# 02-POWER_DC-DC.net
KiCad netlist of a schematic drawn in Altium Designer
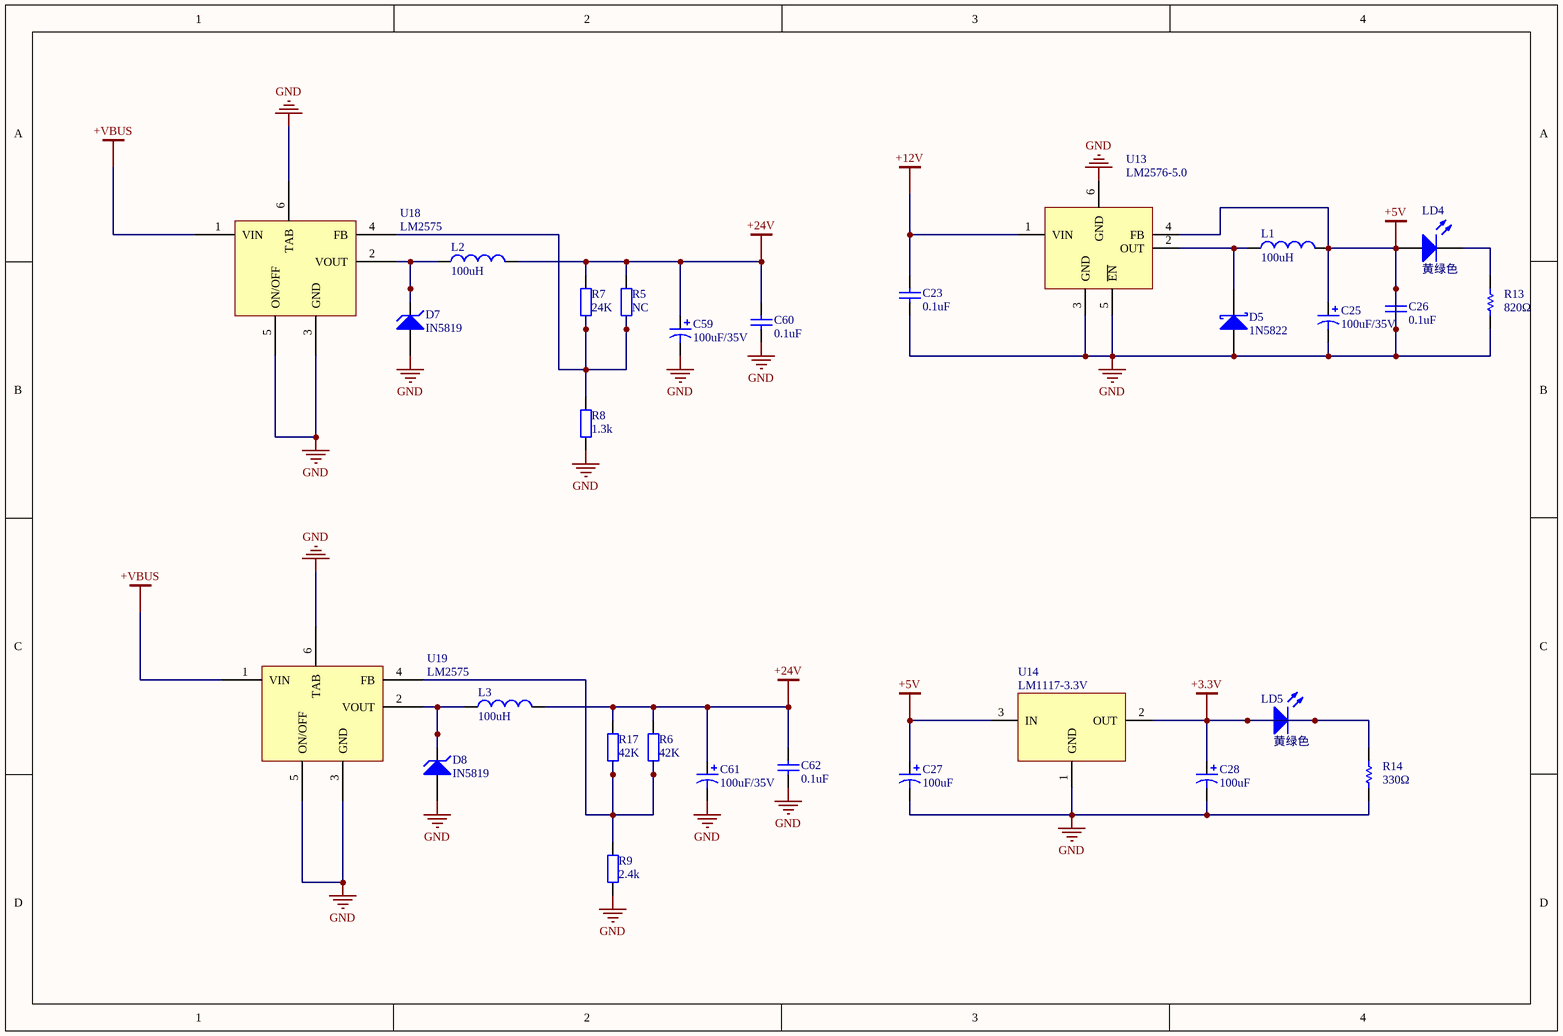
[diagram p0: 02-POWER DC-DC.SchDoc]

(export (version "E")
  (design (tool "Eeschema 10.0.6"))
  (components
    (comp (ref "C23")
      (value "0.1uF")
      (footprint "C0805")
      (description "Capacitor")
      (fields (field (name "Comment") "Cap") (field (name "PUBLISHER") "Altium Limited"))
      (libsource (lib "Lib") (part "Cap"))
    )
    (comp (ref "C25")
      (value "100uF/35V")
      (footprint "SMD-6.3-7.7")
      (description "Polarized Capacitor (Axial)")
      (fields (field (name "Comment") "Cap Pol2") (field (name "PUBLISHER") "Altium Limited"))
      (libsource (lib "Lib") (part "Cap Pol2"))
    )
    (comp (ref "C26")
      (value "0.1uF")
      (footprint "C0805")
      (description "Capacitor")
      (fields (field (name "Comment") "Cap") (field (name "PUBLISHER") "Altium Limited"))
      (libsource (lib "Lib") (part "Cap"))
    )
    (comp (ref "C27")
      (value "100uF")
      (footprint "SMD-6.3-7.7")
      (description "Polarized Capacitor (Axial)")
      (fields (field (name "Comment") "Cap Pol2") (field (name "PUBLISHER") "Altium Limited"))
      (libsource (lib "Lib") (part "Cap Pol2"))
    )
    (comp (ref "C28")
      (value "100uF")
      (footprint "SMD-6.3-7.7")
      (description "Polarized Capacitor (Axial)")
      (fields (field (name "Comment") "Cap Pol2") (field (name "PUBLISHER") "Altium Limited"))
      (libsource (lib "Lib") (part "Cap Pol2"))
    )
    (comp (ref "C59")
      (value "100uF/35V")
      (footprint "SMD-6.3-7.7")
      (description "Polarized Capacitor (Axial)")
      (fields (field (name "Comment") "Cap Pol2") (field (name "PUBLISHER") "Altium Limited"))
      (libsource (lib "Lib") (part "Cap Pol2"))
    )
    (comp (ref "C60")
      (value "0.1uF")
      (footprint "C0805")
      (description "Capacitor")
      (fields (field (name "Comment") "Cap") (field (name "PUBLISHER") "Altium Limited"))
      (libsource (lib "Lib") (part "Cap"))
    )
    (comp (ref "C61")
      (value "100uF/35V")
      (footprint "SMD-6.3-7.7")
      (description "Polarized Capacitor (Axial)")
      (fields (field (name "Comment") "Cap Pol2") (field (name "PUBLISHER") "Altium Limited"))
      (libsource (lib "Lib") (part "Cap Pol2"))
    )
    (comp (ref "C62")
      (value "0.1uF")
      (footprint "C0805")
      (description "Capacitor")
      (fields (field (name "Comment") "Cap") (field (name "PUBLISHER") "Altium Limited"))
      (libsource (lib "Lib") (part "Cap"))
    )
    (comp (ref "D5")
      (value "1N5822")
      (footprint "SMA-L4")
      (description "Schottky Rectifier")
      (fields (field (name "PUBLISHER") "Altium Limited"))
      (libsource (lib "Lib") (part "Diode 10TQ035"))
    )
    (comp (ref "D7")
      (value "IN5819")
      (footprint "SMA-L4")
      (description "Zener Diode")
      (fields (field (name "PUBLISHER") "Altium Limited"))
      (libsource (lib "Lib") (part "D Zener"))
    )
    (comp (ref "D8")
      (value "IN5819")
      (footprint "SMA-L4")
      (description "Zener Diode")
      (fields (field (name "PUBLISHER") "Altium Limited"))
      (libsource (lib "Lib") (part "D Zener"))
    )
    (comp (ref "L1")
      (value "100uH")
      (footprint "L100uH")
      (description "Inductor")
      (fields (field (name "PUBLISHER") "Altium Limited"))
      (libsource (lib "Lib") (part "Inductor"))
    )
    (comp (ref "L2")
      (value "100uH")
      (footprint "L100uH")
      (description "Inductor")
      (fields (field (name "PUBLISHER") "Altium Limited"))
      (libsource (lib "Lib") (part "Inductor"))
    )
    (comp (ref "L3")
      (value "100uH")
      (footprint "L100uH")
      (description "Inductor")
      (fields (field (name "PUBLISHER") "Altium Limited"))
      (libsource (lib "Lib") (part "Inductor"))
    )
    (comp (ref "LD4")
      (value "黄绿色")
      (footprint "LED0805")
      (description "Typical INFRARED GaAs LED")
      (fields (field (name "PUBLISHER") "Altium Limited"))
      (libsource (lib "Lib") (part "LED0"))
    )
    (comp (ref "LD5")
      (value "黄绿色")
      (footprint "LED0805")
      (description "Typical INFRARED GaAs LED")
      (fields (field (name "PUBLISHER") "Altium Limited"))
      (libsource (lib "Lib") (part "LED0"))
    )
    (comp (ref "R5")
      (value "NC")
      (footprint "R0805")
      (description "Resistor")
      (fields (field (name "Comment") "Res2") (field (name "PUBLISHER") "Altium Limited"))
      (libsource (lib "") (part "Res2_1"))
    )
    (comp (ref "R6")
      (value "42K")
      (footprint "R0805")
      (description "Resistor")
      (fields (field (name "Comment") "Res2") (field (name "PUBLISHER") "Altium Limited"))
      (libsource (lib "") (part "Res2_1"))
    )
    (comp (ref "R7")
      (value "24K")
      (footprint "R0805")
      (description "Resistor")
      (fields (field (name "Comment") "Res2") (field (name "PUBLISHER") "Altium Limited"))
      (libsource (lib "Lib") (part "Res2"))
    )
    (comp (ref "R8")
      (value "1.3k")
      (footprint "R0805")
      (description "Resistor")
      (fields (field (name "Comment") "Res2") (field (name "PUBLISHER") "Altium Limited"))
      (libsource (lib "") (part "Res2_1"))
    )
    (comp (ref "R9")
      (value "2.4k")
      (footprint "R0805")
      (description "Resistor")
      (fields (field (name "Comment") "Res2") (field (name "PUBLISHER") "Altium Limited"))
      (libsource (lib "") (part "Res2_1"))
    )
    (comp (ref "R13")
      (value "820Ω")
      (footprint "NTC-10D9")
      (description "Resistor")
      (fields (field (name "PUBLISHER") "Altium Limited"))
      (libsource (lib "Lib") (part "Res1"))
    )
    (comp (ref "R14")
      (value "330Ω")
      (footprint "NTC-10D9")
      (description "Resistor")
      (fields (field (name "PUBLISHER") "Altium Limited"))
      (libsource (lib "Lib") (part "Res1"))
    )
    (comp (ref "R17")
      (value "42K")
      (footprint "R0805")
      (description "Resistor")
      (fields (field (name "Comment") "Res2") (field (name "PUBLISHER") "Altium Limited"))
      (libsource (lib "Lib") (part "Res2"))
    )
    (comp (ref "U13") (value "LM2576-5.0") (footprint "TO-263-5") (libsource (lib "Lib") (part "LM2576-5.0")))
    (comp (ref "U14") (value "LM1117-3.3V") (footprint "SOT-223") (libsource (lib "Lib") (part "LM1117")))
    (comp (ref "U18") (value "LM2575") (footprint "TO-263-5") (libsource (lib "Schlib1") (part "LM2575")))
    (comp (ref "U19") (value "LM2575") (footprint "TO-263-5") (libsource (lib "Schlib1") (part "LM2575")))
  )
  (nets
    (net (code "1") (name "+3.3V") (class "Default")
      (node (ref "C28") (pin "1") (pinfunction "1_1") (pintype "passive"))
      (node (ref "LD5") (pin "1") (pinfunction "A_1") (pintype "passive"))
      (node (ref "LD5") (pin "2") (pinfunction "K_2") (pintype "passive"))
      (node (ref "R14") (pin "2") (pinfunction "2_2") (pintype "passive"))
      (node (ref "U14") (pin "2") (pinfunction "OUT_2") (pintype "passive"))
    )
    (net (code "2") (name "+5V") (class "Default")
      (node (ref "C23") (pin "1") (pinfunction "1_1") (pintype "passive"))
      (node (ref "C25") (pin "1") (pinfunction "1_1") (pintype "passive"))
      (node (ref "C25") (pin "2") (pinfunction "2_2") (pintype "passive"))
      (node (ref "C26") (pin "1") (pinfunction "1_1") (pintype "passive"))
      (node (ref "C26") (pin "2") (pinfunction "2_2") (pintype "passive"))
      (node (ref "C27") (pin "1") (pinfunction "1_1") (pintype "passive"))
      (node (ref "C27") (pin "2") (pinfunction "2_2") (pintype "passive"))
      (node (ref "C28") (pin "2") (pinfunction "2_2") (pintype "passive"))
      (node (ref "C59") (pin "2") (pinfunction "2_2") (pintype "passive"))
      (node (ref "C60") (pin "1") (pinfunction "1_1") (pintype "passive"))
      (node (ref "C61") (pin "2") (pinfunction "2_2") (pintype "passive"))
      (node (ref "C62") (pin "1") (pinfunction "1_1") (pintype "passive"))
      (node (ref "D5") (pin "2") (pinfunction "A_2") (pintype "passive"))
      (node (ref "D7") (pin "1") (pinfunction "A_1") (pintype "passive"))
      (node (ref "D8") (pin "1") (pinfunction "A_1") (pintype "passive"))
      (node (ref "L1") (pin "2") (pinfunction "2_2") (pintype "passive"))
      (node (ref "LD4") (pin "1") (pinfunction "A_1") (pintype "passive"))
      (node (ref "R13") (pin "1") (pinfunction "1_1") (pintype "passive"))
      (node (ref "R14") (pin "1") (pinfunction "1_1") (pintype "passive"))
      (node (ref "R8") (pin "2") (pinfunction "2_2") (pintype "passive"))
      (node (ref "R9") (pin "2") (pinfunction "2_2") (pintype "passive"))
      (node (ref "U13") (pin "3") (pinfunction "GND_3") (pintype "passive"))
      (node (ref "U13") (pin "4") (pinfunction "FB_4") (pintype "passive"))
      (node (ref "U13") (pin "5") (pinfunction "~{EN}_5") (pintype "passive"))
      (node (ref "U13") (pin "6") (pinfunction "GND_6") (pintype "passive"))
      (node (ref "U14") (pin "1") (pinfunction "GND_1") (pintype "passive"))
      (node (ref "U14") (pin "3") (pinfunction "IN_3") (pintype "passive"))
      (node (ref "U18") (pin "3") (pinfunction "GND_3") (pintype "passive"))
      (node (ref "U18") (pin "5") (pinfunction "ON/OFF_5") (pintype "passive"))
      (node (ref "U18") (pin "6") (pinfunction "TAB_6") (pintype "passive"))
      (node (ref "U19") (pin "3") (pinfunction "GND_3") (pintype "passive"))
      (node (ref "U19") (pin "5") (pinfunction "ON/OFF_5") (pintype "passive"))
      (node (ref "U19") (pin "6") (pinfunction "TAB_6") (pintype "passive"))
    )
    (net (code "3") (name "+12V") (class "Default")
      (node (ref "C23") (pin "2") (pinfunction "2_2") (pintype "passive"))
      (node (ref "U13") (pin "1") (pinfunction "VIN_1") (pintype "passive"))
    )
    (net (code "4") (name "+24V") (class "Default")
      (node (ref "C59") (pin "1") (pinfunction "1_1") (pintype "passive"))
      (node (ref "C60") (pin "2") (pinfunction "2_2") (pintype "passive"))
      (node (ref "C61") (pin "1") (pinfunction "1_1") (pintype "passive"))
      (node (ref "C62") (pin "2") (pinfunction "2_2") (pintype "passive"))
      (node (ref "L2") (pin "2") (pinfunction "2_2") (pintype "passive"))
      (node (ref "L3") (pin "2") (pinfunction "2_2") (pintype "passive"))
      (node (ref "R17") (pin "2") (pinfunction "2_2") (pintype "passive"))
      (node (ref "R5") (pin "1") (pinfunction "1_1") (pintype "passive"))
      (node (ref "R6") (pin "1") (pinfunction "1_1") (pintype "passive"))
      (node (ref "R7") (pin "2") (pinfunction "2_2") (pintype "passive"))
    )
    (net (code "5") (name "+VBUS") (class "Default")
      (node (ref "U18") (pin "1") (pinfunction "VIN_1") (pintype "passive"))
      (node (ref "U19") (pin "1") (pinfunction "VIN_1") (pintype "passive"))
    )
    (net (code "6") (name "Net-(D5-K)") (class "Default")
      (node (ref "D5") (pin "1") (pinfunction "K_1") (pintype "passive"))
      (node (ref "L1") (pin "1") (pinfunction "1_1") (pintype "passive"))
      (node (ref "U13") (pin "2") (pinfunction "OUT_2") (pintype "passive"))
    )
    (net (code "7") (name "Net-(D7-K)") (class "Default")
      (node (ref "D7") (pin "2") (pinfunction "K_2") (pintype "passive"))
      (node (ref "L2") (pin "1") (pinfunction "1_1") (pintype "passive"))
      (node (ref "U18") (pin "2") (pinfunction "VOUT_2") (pintype "passive"))
    )
    (net (code "8") (name "Net-(D8-K)") (class "Default")
      (node (ref "D8") (pin "2") (pinfunction "K_2") (pintype "passive"))
      (node (ref "L3") (pin "1") (pinfunction "1_1") (pintype "passive"))
      (node (ref "U19") (pin "2") (pinfunction "VOUT_2") (pintype "passive"))
    )
    (net (code "9") (name "Net-(LD4-K)") (class "Default")
      (node (ref "LD4") (pin "2") (pinfunction "K_2") (pintype "passive"))
      (node (ref "R13") (pin "2") (pinfunction "2_2") (pintype "passive"))
    )
    (net (code "10") (name "Net-(U18-FB)") (class "Default")
      (node (ref "R5") (pin "2") (pinfunction "2_2") (pintype "passive"))
      (node (ref "R7") (pin "1") (pinfunction "1_1") (pintype "passive"))
      (node (ref "R8") (pin "1") (pinfunction "1_1") (pintype "passive"))
      (node (ref "U18") (pin "4") (pinfunction "FB_4") (pintype "passive"))
    )
    (net (code "11") (name "Net-(U19-FB)") (class "Default")
      (node (ref "R17") (pin "1") (pinfunction "1_1") (pintype "passive"))
      (node (ref "R6") (pin "2") (pinfunction "2_2") (pintype "passive"))
      (node (ref "R9") (pin "1") (pinfunction "1_1") (pintype "passive"))
      (node (ref "U19") (pin "4") (pinfunction "FB_4") (pintype "passive"))
    )
  )
)
